# BOC_CAN.net
KiCad netlist of a schematic drawn in Altium Designer
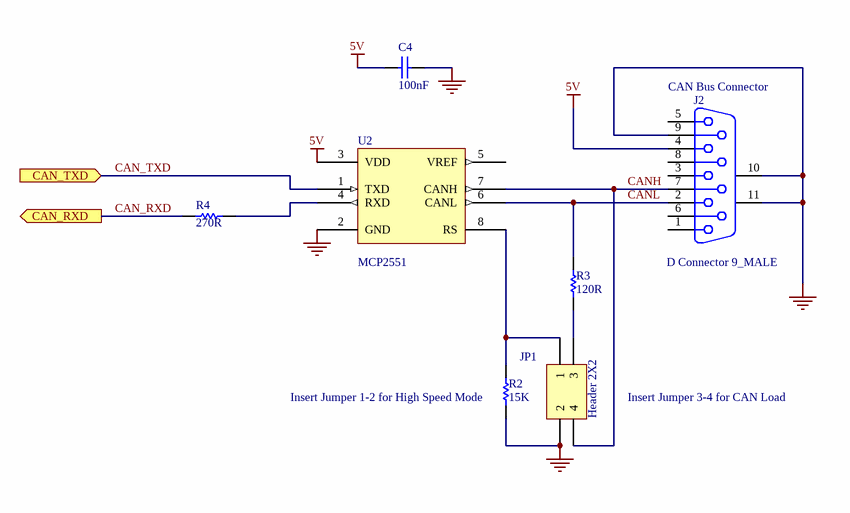
[diagram p0: BOC_CAN.SchDoc]

(export (version "E")
  (design (tool "Eeschema 10.0.6"))
  (components
    (comp (ref "C4")
      (value "100nF")
      (footprint "Altium Nanoboard Project:CC2012-0805")
      (description "Capacitor")
      (libsource (lib "Altium Nanoboard Project") (part "CAP"))
    )
    (comp (ref "J2")
      (value "D Connector 9_MALE")
      (footprint "Altium Nanoboard Project:DSUB1.9_MALE")
      (description "Receptacle Assembly, 9 Position, Right Angle")
      (fields (field (name "MANUFACTURER") "Generic Components") (field (name "PUBLISHER") "Altium Limited"))
      (libsource (lib "Altium Nanoboard Project") (part "D Connector 9_MALE"))
    )
    (comp (ref "JP1")
      (value "Header 2X2")
      (footprint "Altium Nanoboard Project:HDR2X2")
      (description "Header, 2-Pin, Dual row")
      (fields (field (name "MANUFACTURER") "Generic Components") (field (name "PUBLISHER") "Altium Limited"))
      (libsource (lib "Altium Nanoboard Project") (part "Header 2X2"))
    )
    (comp (ref "R2")
      (value "15K")
      (footprint "Altium Nanoboard Project:CC2012-0805")
      (description "Resistor")
      (libsource (lib "Altium Nanoboard Project") (part "RES"))
    )
    (comp (ref "R3")
      (value "120R")
      (footprint "Altium Nanoboard Project:CC2012-0805")
      (description "Resistor")
      (libsource (lib "Altium Nanoboard Project") (part "RES"))
    )
    (comp (ref "R4")
      (value "270R")
      (footprint "Altium Nanoboard Project:CC2012-0805")
      (description "Resistor")
      (libsource (lib "Altium Nanoboard Project") (part "RES"))
    )
    (comp (ref "U2")
      (value "MCP2551")
      (footprint "Altium Nanoboard Project:SOIC8")
      (description "High Speed Can Transceiver")
      (libsource (lib "Altium Nanoboard Project") (part "MCP2551"))
    )
  )
  (nets
    (net (code "1") (name "/CANH") (class "Default")
      (node (ref "J2") (pin "7") (pinfunction "7_7") (pintype "passive"))
      (node (ref "JP1") (pin "4") (pinfunction "4_4") (pintype "passive"))
      (node (ref "U2") (pin "7") (pinfunction "CANH_7") (pintype "output"))
    )
    (net (code "2") (name "/CANL") (class "Default")
      (node (ref "J2") (pin "2") (pinfunction "2_2") (pintype "passive"))
      (node (ref "R3") (pin "2") (pinfunction "2_2") (pintype "passive"))
      (node (ref "U2") (pin "6") (pinfunction "CANL_6") (pintype "output"))
    )
    (net (code "3") (name "/CAN_RXD") (class "Default")
      (node (ref "R4") (pin "1") (pinfunction "1_1") (pintype "passive"))
    )
    (net (code "4") (name "/CAN_TXD") (class "Default")
      (node (ref "U2") (pin "1") (pinfunction "TXD_1") (pintype "input"))
    )
    (net (code "5") (name "5V") (class "Default")
      (node (ref "C4") (pin "1") (pinfunction "1_1") (pintype "passive"))
      (node (ref "J2") (pin "4") (pinfunction "4_4") (pintype "passive"))
      (node (ref "U2") (pin "3") (pinfunction "VDD_3") (pintype "power_in"))
    )
    (net (code "6") (name "GND") (class "Default")
      (node (ref "C4") (pin "2") (pinfunction "2_2") (pintype "passive"))
      (node (ref "J2") (pin "10") (pinfunction "MH1_10") (pintype "passive"))
      (node (ref "J2") (pin "11") (pinfunction "MH2_11") (pintype "passive"))
      (node (ref "J2") (pin "9") (pinfunction "9_9") (pintype "passive"))
      (node (ref "JP1") (pin "2") (pinfunction "2_2") (pintype "passive"))
      (node (ref "R2") (pin "1") (pinfunction "1_1") (pintype "passive"))
      (node (ref "U2") (pin "2") (pinfunction "GND_2") (pintype "power_in"))
    )
    (net (code "7") (name "Net-(JP1-Pad3)") (class "Default")
      (node (ref "JP1") (pin "3") (pinfunction "3_3") (pintype "passive"))
      (node (ref "R3") (pin "1") (pinfunction "1_1") (pintype "passive"))
    )
    (net (code "8") (name "Net-(U2-RS)") (class "Default")
      (node (ref "JP1") (pin "1") (pinfunction "1_1") (pintype "passive"))
      (node (ref "R2") (pin "2") (pinfunction "2_2") (pintype "passive"))
      (node (ref "U2") (pin "8") (pinfunction "RS_8") (pintype "passive"))
    )
    (net (code "9") (name "Net-(U2-RXD)") (class "Default")
      (node (ref "R4") (pin "2") (pinfunction "2_2") (pintype "passive"))
      (node (ref "U2") (pin "4") (pinfunction "RXD_4") (pintype "output"))
    )
    (net (code "10") (name "unconnected-(J2-Pad1)") (class "Default")
      (node (ref "J2") (pin "1") (pinfunction "1_1") (pintype "passive"))
    )
    (net (code "11") (name "unconnected-(J2-Pad3)") (class "Default")
      (node (ref "J2") (pin "3") (pinfunction "3_3") (pintype "passive"))
    )
    (net (code "12") (name "unconnected-(J2-Pad5)") (class "Default")
      (node (ref "J2") (pin "5") (pinfunction "5_5") (pintype "passive"))
    )
    (net (code "13") (name "unconnected-(J2-Pad6)") (class "Default")
      (node (ref "J2") (pin "6") (pinfunction "6_6") (pintype "passive"))
    )
    (net (code "14") (name "unconnected-(J2-Pad8)") (class "Default")
      (node (ref "J2") (pin "8") (pinfunction "8_8") (pintype "passive"))
    )
    (net (code "15") (name "unconnected-(U2-VREF-Pad5)") (class "Default")
      (node (ref "U2") (pin "5") (pinfunction "VREF_5") (pintype "output"))
    )
  )
)
